# ST_LINK_V3E.net
KiCad netlist of a schematic drawn in Altium Designer
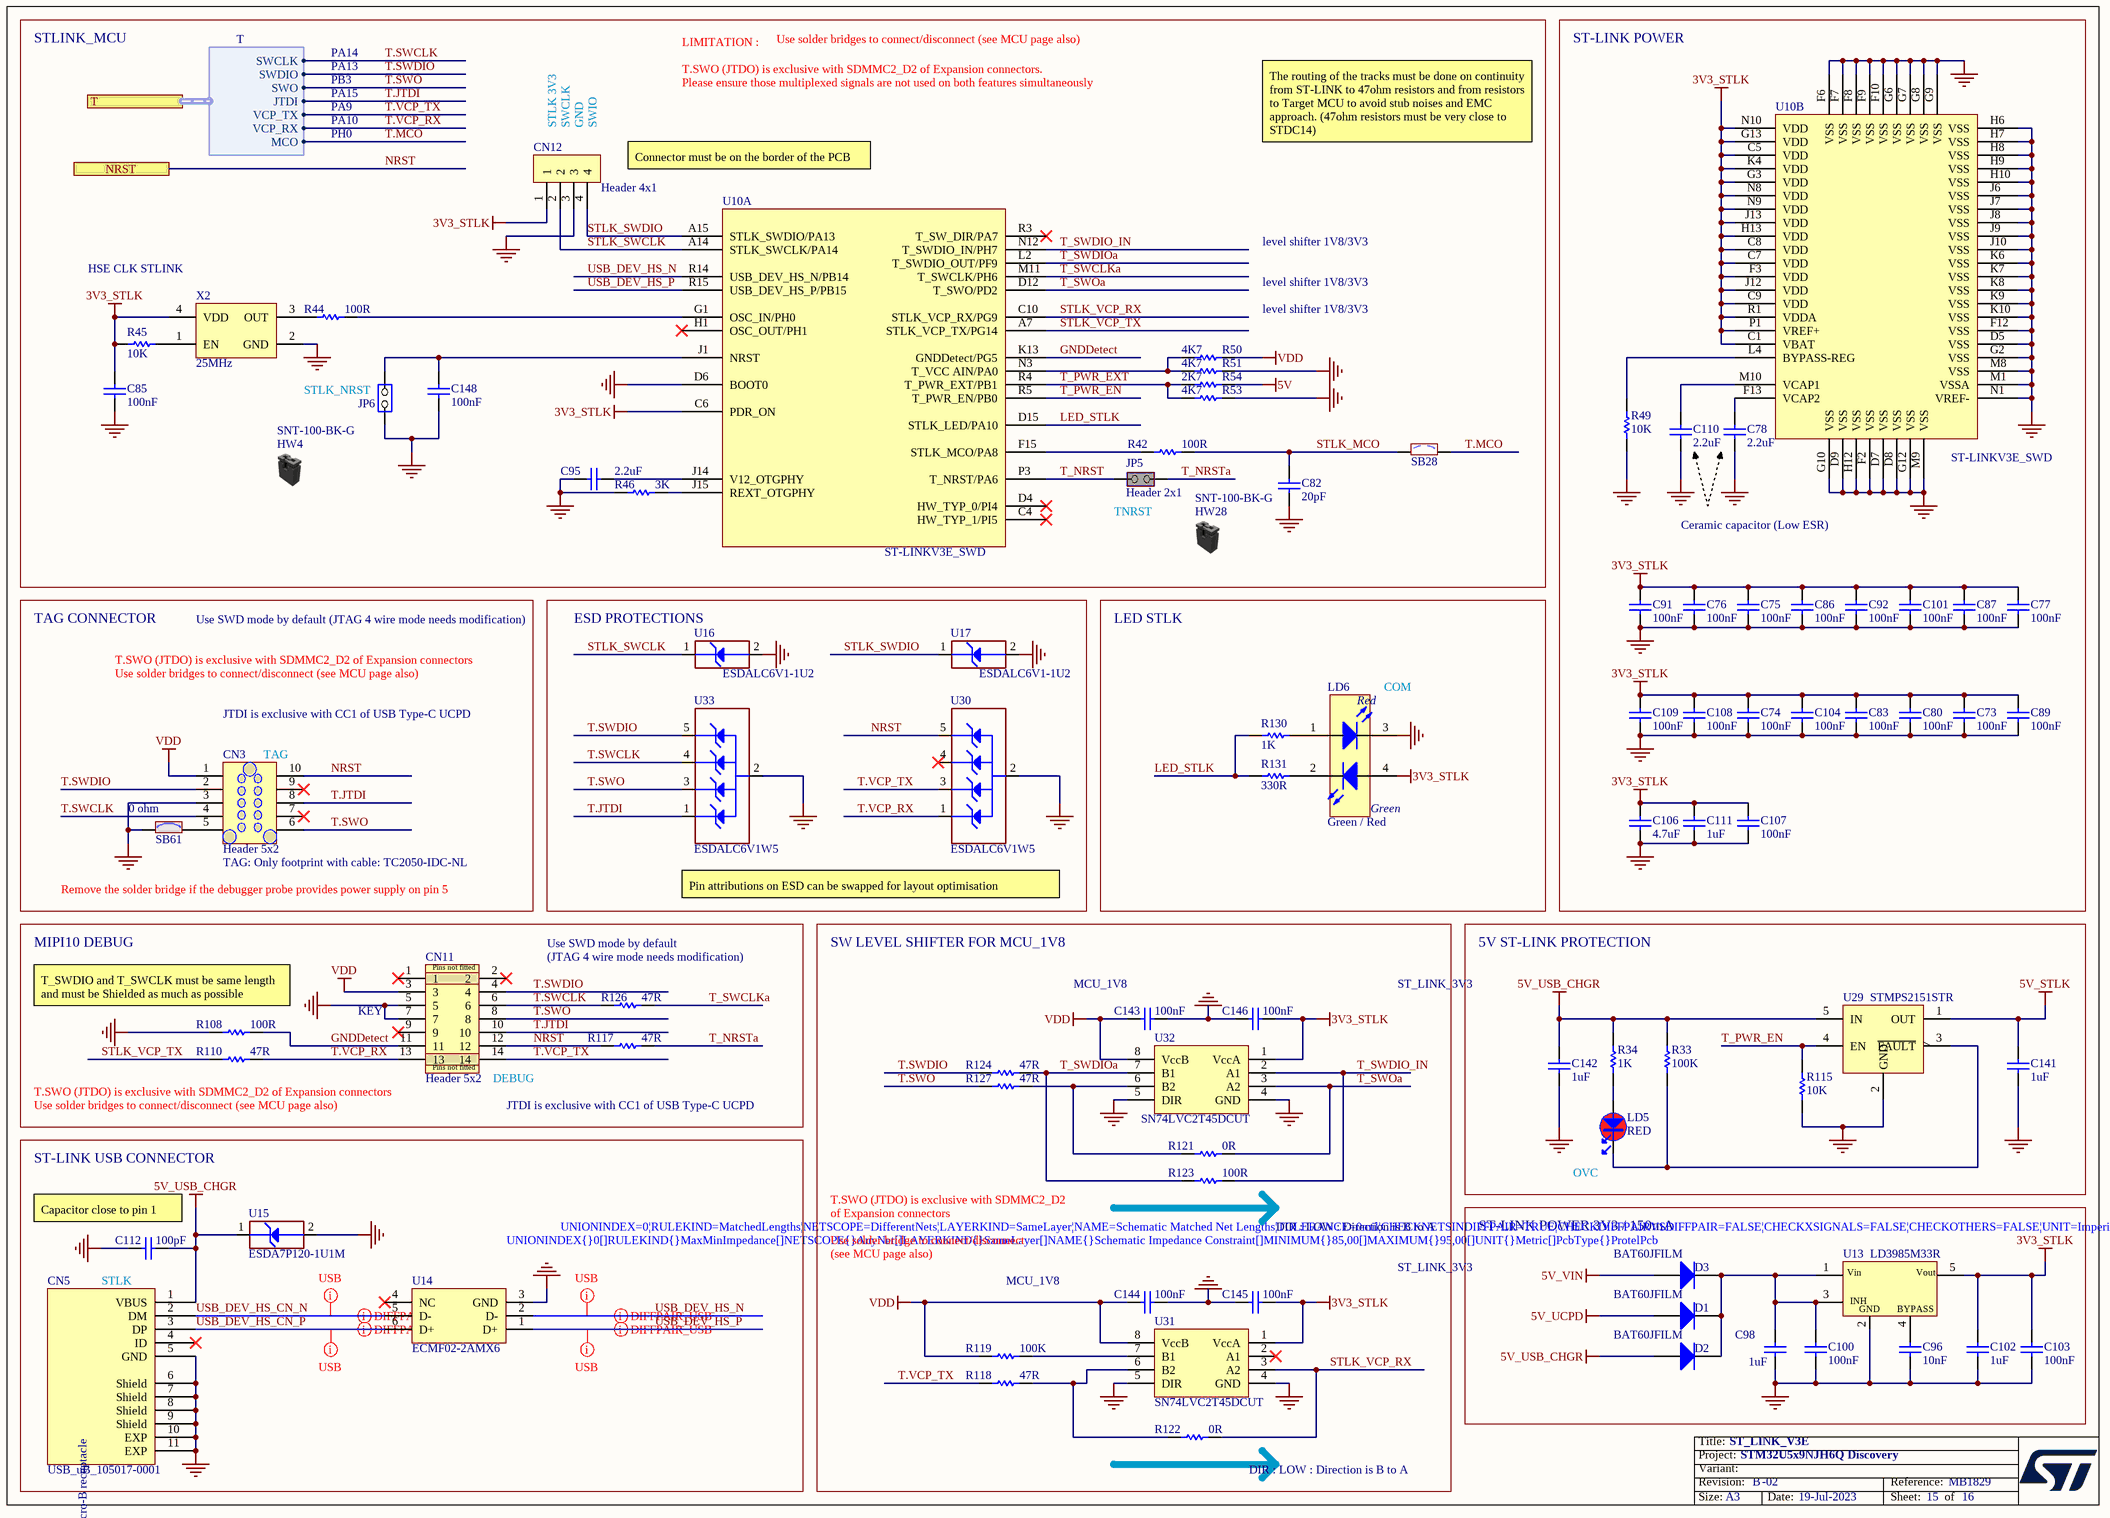
[diagram p0: ST_LINK_V3E.SchDoc]

(export (version "E")
  (design (tool "Eeschema 10.0.6"))
  (components
    (comp (ref "C73")
      (value "100nF")
      (footprint "MCD_PARTS:C0402")
      (description "Capacitor, MLCC, 100nF, 16V, X7R, +/-10%, 0402, T=0.5mm")
      (fields
        (field (name "INTERNAL_PART_NUMBER") "MCD-00006")
        (field (name "MANUFACTURER_PART_NUMBER") "CC0402KRX7R7BB104")
      )
      (libsource (lib "MCD_PARTS_database") (part "Capacitor"))
    )
    (comp (ref "C74")
      (value "100nF")
      (footprint "MCD_PARTS:C0402")
      (description "Capacitor, MLCC, 100nF, 16V, X7R, +/-10%, 0402, T=0.5mm")
      (fields
        (field (name "INTERNAL_PART_NUMBER") "MCD-00006")
        (field (name "MANUFACTURER_PART_NUMBER") "CC0402KRX7R7BB104")
      )
      (libsource (lib "MCD_PARTS_database") (part "Capacitor"))
    )
    (comp (ref "C75")
      (value "100nF")
      (footprint "MCD_PARTS:C0402")
      (description "Capacitor, MLCC, 100nF, 16V, X7R, +/-10%, 0402, T=0.5mm")
      (fields
        (field (name "INTERNAL_PART_NUMBER") "MCD-00006")
        (field (name "MANUFACTURER_PART_NUMBER") "CC0402KRX7R7BB104")
      )
      (libsource (lib "MCD_PARTS_database") (part "Capacitor"))
    )
    (comp (ref "C76")
      (value "100nF")
      (footprint "MCD_PARTS:C0402")
      (description "Capacitor, MLCC, 100nF, 16V, X7R, +/-10%, 0402, T=0.5mm")
      (fields
        (field (name "INTERNAL_PART_NUMBER") "MCD-00006")
        (field (name "MANUFACTURER_PART_NUMBER") "CC0402KRX7R7BB104")
      )
      (libsource (lib "MCD_PARTS_database") (part "Capacitor"))
    )
    (comp (ref "C77")
      (value "100nF")
      (footprint "MCD_PARTS:C0402")
      (description "Capacitor, MLCC, 100nF, 16V, X7R, +/-10%, 0402, T=0.5mm")
      (fields
        (field (name "INTERNAL_PART_NUMBER") "MCD-00006")
        (field (name "MANUFACTURER_PART_NUMBER") "CC0402KRX7R7BB104")
      )
      (libsource (lib "MCD_PARTS_database") (part "Capacitor"))
    )
    (comp (ref "C78")
      (value "2.2uF")
      (footprint "MCD_PARTS:C0603")
      (description "Capacitor, MLCC, 2.2uF, 10V, X5R, +/- 10%, 0603, T=0.8mm")
      (fields
        (field (name "INTERNAL_PART_NUMBER") "MCD-00012")
        (field (name "MANUFACTURER_PART_NUMBER") "CC0603KRX5R6BB225")
      )
      (libsource (lib "MCD_PARTS_database") (part "Capacitor"))
    )
    (comp (ref "C80")
      (value "100nF")
      (footprint "MCD_PARTS:C0402")
      (description "Capacitor, MLCC, 100nF, 16V, X7R, +/-10%, 0402, T=0.5mm")
      (fields
        (field (name "INTERNAL_PART_NUMBER") "MCD-00006")
        (field (name "MANUFACTURER_PART_NUMBER") "CC0402KRX7R7BB104")
      )
      (libsource (lib "MCD_PARTS_database") (part "Capacitor"))
    )
    (comp (ref "C82")
      (value "20pF")
      (footprint "MCD_PARTS:C0402")
      (description "Capacitor, MLCC, 20pF, 50V, NPO, +/- 5%, 0402, T=0.5mm")
      (fields
        (field (name "INTERNAL_PART_NUMBER") "MCD-00016")
        (field (name "MANUFACTURER_PART_NUMBER") "CC0402JRNPO9BN200")
      )
      (libsource (lib "MCD_PARTS_database") (part "Capacitor"))
    )
    (comp (ref "C83")
      (value "100nF")
      (footprint "MCD_PARTS:C0402")
      (description "Capacitor, MLCC, 100nF, 16V, X7R, +/-10%, 0402, T=0.5mm")
      (fields
        (field (name "INTERNAL_PART_NUMBER") "MCD-00006")
        (field (name "MANUFACTURER_PART_NUMBER") "CC0402KRX7R7BB104")
      )
      (libsource (lib "MCD_PARTS_database") (part "Capacitor"))
    )
    (comp (ref "C85")
      (value "100nF")
      (footprint "MCD_PARTS:C0402")
      (description "Capacitor, MLCC, 100nF, 16V, X7R, +/-10%, 0402, T=0.5mm")
      (fields
        (field (name "INTERNAL_PART_NUMBER") "MCD-00006")
        (field (name "MANUFACTURER_PART_NUMBER") "CC0402KRX7R7BB104")
      )
      (libsource (lib "MCD_PARTS_database") (part "Capacitor"))
    )
    (comp (ref "C86")
      (value "100nF")
      (footprint "MCD_PARTS:C0402")
      (description "Capacitor, MLCC, 100nF, 16V, X7R, +/-10%, 0402, T=0.5mm")
      (fields
        (field (name "INTERNAL_PART_NUMBER") "MCD-00006")
        (field (name "MANUFACTURER_PART_NUMBER") "CC0402KRX7R7BB104")
      )
      (libsource (lib "MCD_PARTS_database") (part "Capacitor"))
    )
    (comp (ref "C87")
      (value "100nF")
      (footprint "MCD_PARTS:C0402")
      (description "Capacitor, MLCC, 100nF, 16V, X7R, +/-10%, 0402, T=0.5mm")
      (fields
        (field (name "INTERNAL_PART_NUMBER") "MCD-00006")
        (field (name "MANUFACTURER_PART_NUMBER") "CC0402KRX7R7BB104")
      )
      (libsource (lib "MCD_PARTS_database") (part "Capacitor"))
    )
    (comp (ref "C89")
      (value "100nF")
      (footprint "MCD_PARTS:C0402")
      (description "Capacitor, MLCC, 100nF, 16V, X7R, +/-10%, 0402, T=0.5mm")
      (fields
        (field (name "INTERNAL_PART_NUMBER") "MCD-00006")
        (field (name "MANUFACTURER_PART_NUMBER") "CC0402KRX7R7BB104")
      )
      (libsource (lib "MCD_PARTS_database") (part "Capacitor"))
    )
    (comp (ref "C91")
      (value "100nF")
      (footprint "MCD_PARTS:C0402")
      (description "Capacitor, MLCC, 100nF, 16V, X7R, +/-10%, 0402, T=0.5mm")
      (fields
        (field (name "INTERNAL_PART_NUMBER") "MCD-00006")
        (field (name "MANUFACTURER_PART_NUMBER") "CC0402KRX7R7BB104")
      )
      (libsource (lib "MCD_PARTS_database") (part "Capacitor"))
    )
    (comp (ref "C92")
      (value "100nF")
      (footprint "MCD_PARTS:C0402")
      (description "Capacitor, MLCC, 100nF, 16V, X7R, +/-10%, 0402, T=0.5mm")
      (fields
        (field (name "INTERNAL_PART_NUMBER") "MCD-00006")
        (field (name "MANUFACTURER_PART_NUMBER") "CC0402KRX7R7BB104")
      )
      (libsource (lib "MCD_PARTS_database") (part "Capacitor"))
    )
    (comp (ref "C95")
      (value "2.2uF")
      (footprint "MCD_PARTS:C0603")
      (description "Capacitor, MLCC, 2.2uF, 10V, X5R, +/- 10%, 0603, T=0.8mm")
      (fields
        (field (name "INTERNAL_PART_NUMBER") "MCD-00012")
        (field (name "MANUFACTURER_PART_NUMBER") "CC0603KRX5R6BB225")
      )
      (libsource (lib "MCD_PARTS_database") (part "Capacitor"))
    )
    (comp (ref "C96")
      (value "10nF")
      (footprint "MCD_PARTS:C0402")
      (description "Capacitor, MLCC, 10nF, 16V, X7R, +/-10%, 0402, T=0.5mm")
      (fields
        (field (name "INTERNAL_PART_NUMBER") "MCD-00011")
        (field (name "MANUFACTURER_PART_NUMBER") "CC0402KRX7R7BB103")
      )
      (libsource (lib "MCD_PARTS_database") (part "Capacitor"))
    )
    (comp (ref "C98")
      (value "1uF")
      (footprint "MCD_PARTS:C0402")
      (description "Capacitor, MLCC, 1uF, 25V, X5R, +/-10%, 0402, T=0.5mm")
      (fields (field (name "INTERNAL_PART_NUMBER") "MCD-02609") (field (name "MANUFACTURER") "YAGEO"))
      (libsource (lib "MCD_PARTS_database") (part "Capacitor"))
    )
    (comp (ref "C100")
      (value "100nF")
      (footprint "MCD_PARTS:C0402")
      (description "Capacitor, MLCC, 100nF, 16V, X7R, +/-10%, 0402, T=0.5mm")
      (fields
        (field (name "INTERNAL_PART_NUMBER") "MCD-00006")
        (field (name "MANUFACTURER_PART_NUMBER") "CC0402KRX7R7BB104")
      )
      (libsource (lib "MCD_PARTS_database") (part "Capacitor"))
    )
    (comp (ref "C101")
      (value "100nF")
      (footprint "MCD_PARTS:C0402")
      (description "Capacitor, MLCC, 100nF, 16V, X7R, +/-10%, 0402, T=0.5mm")
      (fields
        (field (name "INTERNAL_PART_NUMBER") "MCD-00006")
        (field (name "MANUFACTURER_PART_NUMBER") "CC0402KRX7R7BB104")
      )
      (libsource (lib "MCD_PARTS_database") (part "Capacitor"))
    )
    (comp (ref "C102")
      (value "1uF")
      (footprint "MCD_PARTS:C0402")
      (description "Capacitor, MLCC, 1uF, 25V, X5R, +/-10%, 0402, T=0.5mm")
      (fields (field (name "INTERNAL_PART_NUMBER") "MCD-02609") (field (name "MANUFACTURER") "YAGEO"))
      (libsource (lib "MCD_PARTS_database") (part "Capacitor"))
    )
    (comp (ref "C103")
      (value "100nF")
      (footprint "MCD_PARTS:C0402")
      (description "Capacitor, MLCC, 100nF, 16V, X7R, +/-10%, 0402, T=0.5mm")
      (fields
        (field (name "INTERNAL_PART_NUMBER") "MCD-00006")
        (field (name "MANUFACTURER_PART_NUMBER") "CC0402KRX7R7BB104")
      )
      (libsource (lib "MCD_PARTS_database") (part "Capacitor"))
    )
    (comp (ref "C104")
      (value "100nF")
      (footprint "MCD_PARTS:C0402")
      (description "Capacitor, MLCC, 100nF, 16V, X7R, +/-10%, 0402, T=0.5mm")
      (fields
        (field (name "INTERNAL_PART_NUMBER") "MCD-00006")
        (field (name "MANUFACTURER_PART_NUMBER") "CC0402KRX7R7BB104")
      )
      (libsource (lib "MCD_PARTS_database") (part "Capacitor"))
    )
    (comp (ref "C106")
      (value "4.7uF")
      (footprint "MCD_PARTS:C0603")
      (description "Capacitor, MLCC, 4.7uF, 16V, X5R, +/-10%, 0603, T=0.8mm")
      (fields
        (field (name "INTERNAL_PART_NUMBER") "MCD-00009")
        (field (name "MANUFACTURER_PART_NUMBER") "CC0603KRX5R7BB475")
      )
      (libsource (lib "MCD_PARTS_database") (part "Capacitor"))
    )
    (comp (ref "C107")
      (value "100nF")
      (footprint "MCD_PARTS:C0402")
      (description "Capacitor, MLCC, 100nF, 16V, X7R, +/-10%, 0402, T=0.5mm")
      (fields
        (field (name "INTERNAL_PART_NUMBER") "MCD-00006")
        (field (name "MANUFACTURER_PART_NUMBER") "CC0402KRX7R7BB104")
      )
      (libsource (lib "MCD_PARTS_database") (part "Capacitor"))
    )
    (comp (ref "C108")
      (value "100nF")
      (footprint "MCD_PARTS:C0402")
      (description "Capacitor, MLCC, 100nF, 16V, X7R, +/-10%, 0402, T=0.5mm")
      (fields
        (field (name "INTERNAL_PART_NUMBER") "MCD-00006")
        (field (name "MANUFACTURER_PART_NUMBER") "CC0402KRX7R7BB104")
      )
      (libsource (lib "MCD_PARTS_database") (part "Capacitor"))
    )
    (comp (ref "C109")
      (value "100nF")
      (footprint "MCD_PARTS:C0402")
      (description "Capacitor, MLCC, 100nF, 16V, X7R, +/-10%, 0402, T=0.5mm")
      (fields
        (field (name "INTERNAL_PART_NUMBER") "MCD-00006")
        (field (name "MANUFACTURER_PART_NUMBER") "CC0402KRX7R7BB104")
      )
      (libsource (lib "MCD_PARTS_database") (part "Capacitor"))
    )
    (comp (ref "C110")
      (value "2.2uF")
      (footprint "MCD_PARTS:C0603")
      (description "Capacitor, MLCC, 2.2uF, 10V, X5R, +/- 10%, 0603, T=0.8mm")
      (fields
        (field (name "INTERNAL_PART_NUMBER") "MCD-00012")
        (field (name "MANUFACTURER_PART_NUMBER") "CC0603KRX5R6BB225")
      )
      (libsource (lib "MCD_PARTS_database") (part "Capacitor"))
    )
    (comp (ref "C111")
      (value "1uF")
      (footprint "MCD_PARTS:C0402")
      (description "Capacitor, MLCC, 1uF, 25V, X5R, +/-10%, 0402, T=0.5mm")
      (fields (field (name "INTERNAL_PART_NUMBER") "MCD-02609") (field (name "MANUFACTURER") "YAGEO"))
      (libsource (lib "MCD_PARTS_database") (part "Capacitor"))
    )
    (comp (ref "C112")
      (value "100pF")
      (footprint "MCD_PARTS:C0402")
      (description "Capacitor, MLCC, 100pF, 50V, NPO, +/-5%, 0402, T=0.5mm")
      (fields
        (field (name "INTERNAL_PART_NUMBER") "MCD-00205")
        (field (name "MANUFACTURER_PART_NUMBER") "CC0402JRNPO9BN101")
      )
      (libsource (lib "MCD_PARTS_database") (part "Capacitor"))
    )
    (comp (ref "C141")
      (value "1uF")
      (footprint "MCD_PARTS:C0402")
      (description "Capacitor, MLCC, 1uF, 25V, X5R, +/-10%, 0402, T=0.5mm")
      (fields (field (name "INTERNAL_PART_NUMBER") "MCD-02609") (field (name "MANUFACTURER") "YAGEO"))
      (libsource (lib "MCD_PARTS_database") (part "Capacitor"))
    )
    (comp (ref "C142")
      (value "1uF")
      (footprint "MCD_PARTS:C0402")
      (description "Capacitor, MLCC, 1uF, 25V, X5R, +/-10%, 0402, T=0.5mm")
      (fields (field (name "INTERNAL_PART_NUMBER") "MCD-02609") (field (name "MANUFACTURER") "YAGEO"))
      (libsource (lib "MCD_PARTS_database") (part "Capacitor"))
    )
    (comp (ref "C143")
      (value "100nF")
      (footprint "MCD_PARTS:C0402")
      (description "Capacitor, MLCC, 100nF, 16V, X7R, +/-10%, 0402, T=0.5mm")
      (fields
        (field (name "INTERNAL_PART_NUMBER") "MCD-00006")
        (field (name "MANUFACTURER_PART_NUMBER") "CC0402KRX7R7BB104")
      )
      (libsource (lib "MCD_PARTS_database") (part "Capacitor"))
    )
    (comp (ref "C144")
      (value "100nF")
      (footprint "MCD_PARTS:C0402")
      (description "Capacitor, MLCC, 100nF, 16V, X7R, +/-10%, 0402, T=0.5mm")
      (fields
        (field (name "INTERNAL_PART_NUMBER") "MCD-00006")
        (field (name "MANUFACTURER_PART_NUMBER") "CC0402KRX7R7BB104")
      )
      (libsource (lib "MCD_PARTS_database") (part "Capacitor"))
    )
    (comp (ref "C145")
      (value "100nF")
      (footprint "MCD_PARTS:C0402")
      (description "Capacitor, MLCC, 100nF, 16V, X7R, +/-10%, 0402, T=0.5mm")
      (fields
        (field (name "INTERNAL_PART_NUMBER") "MCD-00006")
        (field (name "MANUFACTURER_PART_NUMBER") "CC0402KRX7R7BB104")
      )
      (libsource (lib "MCD_PARTS_database") (part "Capacitor"))
    )
    (comp (ref "C146")
      (value "100nF")
      (footprint "MCD_PARTS:C0402")
      (description "Capacitor, MLCC, 100nF, 16V, X7R, +/-10%, 0402, T=0.5mm")
      (fields
        (field (name "INTERNAL_PART_NUMBER") "MCD-00006")
        (field (name "MANUFACTURER_PART_NUMBER") "CC0402KRX7R7BB104")
      )
      (libsource (lib "MCD_PARTS_database") (part "Capacitor"))
    )
    (comp (ref "C148")
      (value "100nF")
      (footprint "MCD_PARTS:C0402")
      (description "Capacitor, MLCC, 100nF, 16V, X7R, +/-10%, 0402, T=0.5mm")
      (fields
        (field (name "INTERNAL_PART_NUMBER") "MCD-00006")
        (field (name "MANUFACTURER_PART_NUMBER") "CC0402KRX7R7BB104")
      )
      (libsource (lib "MCD_PARTS_database") (part "Capacitor"))
    )
    (comp (ref "CN3")
      (value "Header 5x2")
      (footprint "MCD_PARTS:CON_TAG-C_TC2050-IDC-NL")
      (description "Header_Plug-of-nails, 5x2, 1.27mm, No legs")
      (fields
        (field (name "INTERNAL_PART_NUMBER") "MCD-00031")
        (field (name "MANUFACTURER_PART_NUMBER") "TC2050-IDC-NL-FP")
      )
      (libsource (lib "MCD_PARTS_database") (part "Tag-10-C"))
    )
    (comp (ref "CN5")
      (value "USB_uB_105017-0001")
      (footprint "MCD_PARTS:CON_USBMICROB_MOLEX_105017-0001_H2P90")
      (description "MicroUSB_TypeB, 5pins, 0.65mm, RA, SMD, T=2.9mm")
      (fields
        (field (name "INTERNAL_PART_NUMBER") "MCD-00028")
        (field (name "MANUFACTURER_PART_NUMBER") "1050170001")
      )
      (libsource (lib "MCD_PARTS_database") (part "USB_uB_105017.0001"))
    )
    (comp (ref "CN11")
      (value "Header 5x2")
      (footprint "MCD_PARTS:CON_STDC14_Receiver_MEDIUM__3D_FTSH-105-01-L-DV-K")
      (description "Header_MIPI10, 5x2, 1.27mm, VR, SMD, T=6.1mm")
      (fields (field (name "INTERNAL_PART_NUMBER") "MCD-02021") (field (name "MANUFACTURER") "SAMTEC"))
      (libsource (lib "MCD_PARTS_database") (part "Header 7x2_MIPI10_on_STDC14"))
    )
    (comp (ref "CN12")
      (value "Header 4x1")
      (footprint "MCD_PARTS:CON_SAMTEC_TSW-104-07-G-S")
      (description "Header, 4x1, 2.54mm, VR, TH, T=5.84mm/2.54mm")
      (fields
        (field (name "INTERNAL_PART_NUMBER") "MCD-00029")
        (field (name "MANUFACTURER_PART_NUMBER") "TSW-104-07-G-S")
      )
      (libsource (lib "MCD_PARTS_database") (part "Header 4x1"))
    )
    (comp (ref "D1")
      (value "BAT60JFILM")
      (footprint "MCD_PARTS:DIO_SOD323")
      (fields
        (field (name "INTERNAL_PART_NUMBER") "MCD-00034")
        (field (name "MANUFACTURER") "STMICROELECTRONICS")
        (field (name "BMS_PART_NUMBER") "9151097")
      )
      (libsource (lib "MCD_PARTS_database") (part "BAT60JFILM"))
    )
    (comp (ref "D2")
      (value "BAT60JFILM")
      (footprint "MCD_PARTS:DIO_SOD323")
      (fields
        (field (name "INTERNAL_PART_NUMBER") "MCD-00034")
        (field (name "MANUFACTURER") "STMICROELECTRONICS")
        (field (name "BMS_PART_NUMBER") "9151097")
      )
      (libsource (lib "MCD_PARTS_database") (part "BAT60JFILM"))
    )
    (comp (ref "D3")
      (value "BAT60JFILM")
      (footprint "MCD_PARTS:DIO_SOD323")
      (fields
        (field (name "INTERNAL_PART_NUMBER") "MCD-00034")
        (field (name "MANUFACTURER") "STMICROELECTRONICS")
        (field (name "BMS_PART_NUMBER") "9151097")
      )
      (libsource (lib "MCD_PARTS_database") (part "BAT60JFILM"))
    )
    (comp (ref "HW4")
      (value "SNT-100-BK-G")
      (description "SHUNT 2.54mm BLACK")
      (fields (field (name "INTERNAL_PART_NUMBER") "MCD-00043") (field (name "MANUFACTURER") "SAMTEC"))
      (libsource (lib "MCD_PARTS_database") (part "Shunt Black 2.54mm"))
    )
    (comp (ref "HW28")
      (value "SNT-100-BK-G")
      (description "SHUNT 2.54mm BLACK")
      (fields (field (name "INTERNAL_PART_NUMBER") "MCD-00043") (field (name "MANUFACTURER") "SAMTEC"))
      (libsource (lib "MCD_PARTS_database") (part "Shunt Black 2.54mm"))
    )
    (comp (ref "JP5")
      (value "Header 2x1")
      (footprint "MCD_PARTS:CON_SAMTEC_TSW-102-07-G-S")
      (description "Header, 2x1, 2.54mm, VR, TH, T=5.84mm/2.54mm")
      (fields (field (name "INTERNAL_PART_NUMBER") "MCD-01904") (field (name "MANUFACTURER") "SAMTEC"))
      (libsource (lib "MCD_PARTS_database") (part "Jumper_Header 2x1 Fitted"))
    )
    (comp (ref "JP6")
      (value "Jumper_Header 2x1")
      (footprint "MCD_PARTS:CON_SAMTEC_TSW-102-07-G-S")
      (description "Header, 2x1, 2.54mm, VR, TH, T=5.84mm/2.54mm")
      (fields
        (field (name "INTERNAL_PART_NUMBER") "MCD-00045")
        (field (name "MANUFACTURER_PART_NUMBER") "TSW-102-07-G-S")
      )
      (libsource (lib "MCD_PARTS_database") (part "Jumper_Header 2x1"))
    )
    (comp (ref "LD5")
      (value "RED")
      (footprint "MCD_PARTS:LED_0603_OSRAM_LS-Q976-NR-1_RED_1A2K_H0P8")
      (description "LED Red, 0603 SMD, Forward Voltage Typ=2V, Max=2.5V")
      (fields
        (field (name "INTERNAL_PART_NUMBER") "MCD-00586")
        (field (name "MANUFACTURER_PART_NUMBER") "LS Q976-NR-1")
      )
      (libsource (lib "MCD_PARTS_database") (part "LED_red"))
    )
    (comp (ref "LD6")
      (value "Green / Red")
      (footprint "LED_BI-GR_WE-150141SV73110")
      (description "LED Bicolor, Green/Red, 2V, 20mA,  4-PLCC")
      (fields
        (field (name "INTERNAL_PART_NUMBER") "MCD-02631")
        (field (name "MANUFACTURER") "WURTH ELEKTRONIK")
      )
      (libsource (lib "MCD_PARTS_database") (part "LED_BICOLOR"))
    )
    (comp (ref "R33")
      (value "100K")
      (footprint "MCD_PARTS:R0402")
      (description "Resistor, 100K, 0402, +/-1%, 1/16W")
      (fields
        (field (name "INTERNAL_PART_NUMBER") "MCD-00059")
        (field (name "MANUFACTURER_PART_NUMBER") "RC0402FR-07100KL")
      )
      (libsource (lib "MCD_PARTS_database") (part "Resistor"))
    )
    (comp (ref "R34")
      (value "1K")
      (footprint "MCD_PARTS:R0402")
      (description "Resistor, 1K, 0402, +/-1%,1/16W")
      (fields
        (field (name "INTERNAL_PART_NUMBER") "MCD-00061")
        (field (name "MANUFACTURER_PART_NUMBER") "RC0402FR-071KL")
      )
      (libsource (lib "MCD_PARTS_database") (part "Resistor"))
    )
    (comp (ref "R42")
      (value "100R")
      (footprint "MCD_PARTS:R0402")
      (description "Resistor, 100R, 0402, +/- 1%, 1/16W")
      (fields
        (field (name "INTERNAL_PART_NUMBER") "MCD-00067")
        (field (name "MANUFACTURER_PART_NUMBER") "RC0402FR-07100RL")
      )
      (libsource (lib "MCD_PARTS_database") (part "Resistor"))
    )
    (comp (ref "R44")
      (value "100R")
      (footprint "MCD_PARTS:R0402")
      (description "Resistor, 100R, 0402, +/- 1%, 1/16W")
      (fields
        (field (name "INTERNAL_PART_NUMBER") "MCD-00067")
        (field (name "MANUFACTURER_PART_NUMBER") "RC0402FR-07100RL")
      )
      (libsource (lib "MCD_PARTS_database") (part "Resistor"))
    )
    (comp (ref "R45")
      (value "10K")
      (footprint "MCD_PARTS:R0402")
      (description "Resistor, 10K, 0402, +/-1%, 1/16W")
      (fields
        (field (name "INTERNAL_PART_NUMBER") "MCD-00053")
        (field (name "MANUFACTURER_PART_NUMBER") "RC0402FR-0710KL")
      )
      (libsource (lib "MCD_PARTS_database") (part "Resistor"))
    )
    (comp (ref "R46")
      (value "3K")
      (footprint "MCD_PARTS:R0402")
      (description "Resistor, 3K, 0402, +/-1%, 1/16W")
      (fields
        (field (name "INTERNAL_PART_NUMBER") "MCD-00185")
        (field (name "MANUFACTURER_PART_NUMBER") "RC0402FR-073KL")
      )
      (libsource (lib "MCD_PARTS_database") (part "Resistor"))
    )
    (comp (ref "R49")
      (value "10K")
      (footprint "MCD_PARTS:R0402")
      (description "Resistor, 10K, 0402, +/-1%, 1/16W")
      (fields
        (field (name "INTERNAL_PART_NUMBER") "MCD-00053")
        (field (name "MANUFACTURER_PART_NUMBER") "RC0402FR-0710KL")
      )
      (libsource (lib "MCD_PARTS_database") (part "Resistor"))
    )
    (comp (ref "R50")
      (value "4K7")
      (footprint "MCD_PARTS:R0402")
      (description "Resistor, 4K7, 0402, +/-1%, 1/16W")
      (fields
        (field (name "INTERNAL_PART_NUMBER") "MCD-00065")
        (field (name "MANUFACTURER_PART_NUMBER") "RC0402FR-074K7L")
      )
      (libsource (lib "MCD_PARTS_database") (part "Resistor"))
    )
    (comp (ref "R51")
      (value "4K7")
      (footprint "MCD_PARTS:R0402")
      (description "Resistor, 4K7, 0402, +/-1%, 1/16W")
      (fields
        (field (name "INTERNAL_PART_NUMBER") "MCD-00065")
        (field (name "MANUFACTURER_PART_NUMBER") "RC0402FR-074K7L")
      )
      (libsource (lib "MCD_PARTS_database") (part "Resistor"))
    )
    (comp (ref "R53")
      (value "4K7")
      (footprint "MCD_PARTS:R0402")
      (description "Resistor, 4K7, 0402, +/-1%, 1/16W")
      (fields
        (field (name "INTERNAL_PART_NUMBER") "MCD-00065")
        (field (name "MANUFACTURER_PART_NUMBER") "RC0402FR-074K7L")
      )
      (libsource (lib "MCD_PARTS_database") (part "Resistor"))
    )
    (comp (ref "R54")
      (value "2K7")
      (footprint "MCD_PARTS:R0402")
      (description "Resistor, 2K7, 0402, +/-1%, 1/16W")
      (fields
        (field (name "INTERNAL_PART_NUMBER") "MCD-00055")
        (field (name "MANUFACTURER_PART_NUMBER") "RC0402FR-072K7L")
      )
      (libsource (lib "MCD_PARTS_database") (part "Resistor"))
    )
    (comp (ref "R108")
      (value "100R")
      (footprint "MCD_PARTS:R0402")
      (description "Resistor, 100R, 0402, +/- 1%, 1/16W")
      (fields
        (field (name "INTERNAL_PART_NUMBER") "MCD-00067")
        (field (name "MANUFACTURER_PART_NUMBER") "RC0402FR-07100RL")
      )
      (libsource (lib "MCD_PARTS_database") (part "Resistor"))
    )
    (comp (ref "R110")
      (value "47R")
      (footprint "MCD_PARTS:R0402")
      (description "Resistor, 47R, 0402, +/-1%, 1/16W")
      (fields
        (field (name "INTERNAL_PART_NUMBER") "MCD-00481")
        (field (name "MANUFACTURER_PART_NUMBER") "RC0402FR-0747RL")
      )
      (libsource (lib "MCD_PARTS_database") (part "Resistor"))
    )
    (comp (ref "R115")
      (value "10K")
      (footprint "MCD_PARTS:R0402")
      (description "Resistor, 10K, 0402, +/-1%, 1/16W")
      (fields
        (field (name "INTERNAL_PART_NUMBER") "MCD-00053")
        (field (name "MANUFACTURER_PART_NUMBER") "RC0402FR-0710KL")
      )
      (libsource (lib "MCD_PARTS_database") (part "Resistor"))
    )
    (comp (ref "R117")
      (value "47R")
      (footprint "MCD_PARTS:R0402")
      (description "Resistor, 47R, 0402, +/-1%, 1/16W")
      (fields
        (field (name "INTERNAL_PART_NUMBER") "MCD-00481")
        (field (name "MANUFACTURER_PART_NUMBER") "RC0402FR-0747RL")
      )
      (libsource (lib "MCD_PARTS_database") (part "Resistor"))
    )
    (comp (ref "R118")
      (value "47R")
      (footprint "MCD_PARTS:R0402")
      (description "Resistor, 47R, 0402, +/-1%, 1/16W")
      (fields
        (field (name "INTERNAL_PART_NUMBER") "MCD-00481")
        (field (name "MANUFACTURER_PART_NUMBER") "RC0402FR-0747RL")
      )
      (libsource (lib "MCD_PARTS_database") (part "Resistor"))
    )
    (comp (ref "R119")
      (value "100K")
      (footprint "MCD_PARTS:R0402")
      (description "Resistor, 100K, 0402, +/-1%, 1/16W")
      (fields
        (field (name "INTERNAL_PART_NUMBER") "MCD-00059")
        (field (name "MANUFACTURER_PART_NUMBER") "RC0402FR-07100KL")
      )
      (libsource (lib "MCD_PARTS_database") (part "Resistor"))
    )
    (comp (ref "R121")
      (value "0R")
      (footprint "MCD_PARTS:R0402")
      (description "Resistor, 0R, 0402, +/-5%, 1/16W")
      (fields
        (field (name "INTERNAL_PART_NUMBER") "MCD-00052")
        (field (name "MANUFACTURER_PART_NUMBER") "RC0402JR-070RL")
      )
      (libsource (lib "MCD_PARTS_database") (part "Resistor"))
    )
    (comp (ref "R122")
      (value "0R")
      (footprint "MCD_PARTS:R0402")
      (description "Resistor, 0R, 0402, +/-5%, 1/16W")
      (fields
        (field (name "INTERNAL_PART_NUMBER") "MCD-00052")
        (field (name "MANUFACTURER_PART_NUMBER") "RC0402JR-070RL")
      )
      (libsource (lib "MCD_PARTS_database") (part "Resistor"))
    )
    (comp (ref "R123")
      (value "100R")
      (footprint "MCD_PARTS:R0402")
      (description "Resistor, 100R, 0402, +/- 1%, 1/16W")
      (fields
        (field (name "INTERNAL_PART_NUMBER") "MCD-00067")
        (field (name "MANUFACTURER_PART_NUMBER") "RC0402FR-07100RL")
      )
      (libsource (lib "MCD_PARTS_database") (part "Resistor"))
    )
    (comp (ref "R124")
      (value "47R")
      (footprint "MCD_PARTS:R0402")
      (description "Resistor, 47R, 0402, +/-1%, 1/16W")
      (fields
        (field (name "INTERNAL_PART_NUMBER") "MCD-00481")
        (field (name "MANUFACTURER_PART_NUMBER") "RC0402FR-0747RL")
      )
      (libsource (lib "MCD_PARTS_database") (part "Resistor"))
    )
    (comp (ref "R126")
      (value "47R")
      (footprint "MCD_PARTS:R0402")
      (description "Resistor, 47R, 0402, +/-1%, 1/16W")
      (fields
        (field (name "INTERNAL_PART_NUMBER") "MCD-00481")
        (field (name "MANUFACTURER_PART_NUMBER") "RC0402FR-0747RL")
      )
      (libsource (lib "MCD_PARTS_database") (part "Resistor"))
    )
    (comp (ref "R127")
      (value "47R")
      (footprint "MCD_PARTS:R0402")
      (description "Resistor, 47R, 0402, +/-1%, 1/16W")
      (fields
        (field (name "INTERNAL_PART_NUMBER") "MCD-00481")
        (field (name "MANUFACTURER_PART_NUMBER") "RC0402FR-0747RL")
      )
      (libsource (lib "MCD_PARTS_database") (part "Resistor"))
    )
    (comp (ref "R130")
      (value "1K")
      (footprint "MCD_PARTS:R0402")
      (description "Resistor, 1K, 0402, +/-1%,1/16W")
      (fields
        (field (name "INTERNAL_PART_NUMBER") "MCD-00061")
        (field (name "MANUFACTURER_PART_NUMBER") "RC0402FR-071KL")
      )
      (libsource (lib "MCD_PARTS_database") (part "Resistor"))
    )
    (comp (ref "R131")
      (value "330R")
      (footprint "MCD_PARTS:R0402")
      (description "Resistor, 330R, 0402, +/-1%, 1/16W")
      (fields
        (field (name "INTERNAL_PART_NUMBER") "MCD-00062")
        (field (name "MANUFACTURER_PART_NUMBER") "RC0402FR-07330RL")
      )
      (libsource (lib "MCD_PARTS_database") (part "Resistor"))
    )
    (comp (ref "SB28")
      (value "SB_OFF")
      (footprint "MCD_PARTS:SOLDER-BRIDGE_R0402-0R")
      (description "Solder Bridge 0402 OFF")
      (fields
        (field (name "INTERNAL_PART_NUMBER") "MCD-02162")
        (field (name "MANUFACTURER_PART_NUMBER") "RC0402JR-070RL")
      )
      (libsource (lib "MCD_PARTS_database") (part "SB_OFF"))
    )
    (comp (ref "SB61")
      (value "0 ohm")
      (footprint "SOLDER-BRIDGE_R0402-0R")
      (description "Solder Bridge 0402 ON")
      (fields (field (name "INTERNAL_PART_NUMBER") "MCD-01618") (field (name "MANUFACTURER") "YAGEO"))
      (libsource (lib "MCD_PARTS_database") (part "SB_ON"))
    )
    (comp (ref "U10")
      (value "ST-LINKV3E_SWD")
      (footprint "MCD_PARTS:ICC_UFBGA201_176+25_10X10_P065")
      (description "STM32F723IEK  (STM32F7) BGA176")
      (fields
        (field (name "INTERNAL_PART_NUMBER") "MCD-00596")
        (field (name "MANUFACTURER_PART_NUMBER") "STM32F723IEK6")
      )
      (libsource (lib "MCD_PARTS_database") (part "ST-LINKV3E_SWD"))
    )
    (comp (ref "U13")
      (value "LD3985M33R")
      (footprint "MCD_PARTS:REG_SOT23-5L")
      (description "Ultra low drop-low noise BiCMOS voltage, regulators low ESR capacitors compatible")
      (fields
        (field (name "INTERNAL_PART_NUMBER") "MCD-00086")
        (field (name "MANUFACTURER") "STMICROELECTRONICS")
      )
      (libsource (lib "MCD_PARTS_database") (part "LD3985M33R"))
    )
    (comp (ref "U14")
      (value "ECMF02-2AMX6")
      (footprint "MCD_PARTS:ESD_QFN-6L_1P7X1P5_P050")
      (description "Common mode filter with ESD protection for USB 2.0 interface")
      (fields
        (field (name "INTERNAL_PART_NUMBER") "MCD-00649")
        (field (name "MANUFACTURER") "STMICROELECTRONICS")
      )
      (libsource (lib "MCD_PARTS_database") (part "ECMF02-2AMX6"))
    )
    (comp (ref "U15")
      (value "ESDA7P120-1U1M")
      (footprint "MCD_PARTS:ESD_QFN1610_2N_1K_2A")
      (description "High power transient voltage suppressor")
      (fields
        (field (name "INTERNAL_PART_NUMBER") "MCD-01026")
        (field (name "MANUFACTURER") "STMICROELECTRONICS")
      )
      (libsource (lib "MCD_PARTS_database") (part "ESD-TRANSIL"))
    )
    (comp (ref "U16")
      (value "ESDALC6V1-1U2")
      (footprint "MCD_PARTS:ESD_ST0201")
      (description "ESD protection 6V1")
      (fields
        (field (name "INTERNAL_PART_NUMBER") "MCD-00170")
        (field (name "MANUFACTURER") "STMICROELECTRONICS")
      )
      (libsource (lib "MCD_PARTS_database") (part "ESD-TRANSIL"))
    )
    (comp (ref "U17")
      (value "ESDALC6V1-1U2")
      (footprint "MCD_PARTS:ESD_ST0201")
      (description "ESD protection 6V1")
      (fields
        (field (name "INTERNAL_PART_NUMBER") "MCD-00170")
        (field (name "MANUFACTURER") "STMICROELECTRONICS")
      )
      (libsource (lib "MCD_PARTS_database") (part "ESD-TRANSIL"))
    )
    (comp (ref "U29")
      (value "STMPS2151STR")
      (footprint "MCD_PARTS:MOS_SOT23-5L")
      (description "500mA, Enhanced single channel power switches with active high enable pin")
      (fields
        (field (name "INTERNAL_PART_NUMBER") "MCD-00159")
        (field (name "MANUFACTURER") "STMICROELECTRONICS")
      )
      (libsource (lib "MCD_PARTS_database") (part "STMPS2151STR"))
    )
    (comp (ref "U30")
      (value "ESDALC6V1W5")
      (footprint "MCD_PARTS:ESD_SOT323-5L")
      (description "Dual Transil array for ESD protection")
      (fields
        (field (name "INTERNAL_PART_NUMBER") "MCD-00136")
        (field (name "MANUFACTURER") "STMICROELECTRONICS")
      )
      (libsource (lib "MCD_PARTS_database") (part "ESDALC6V1W5"))
    )
    (comp (ref "U31")
      (value "SN74LVC2T45DCUT")
      (footprint "MCD_PARTS:ICC_VSSOP8_DCU_R-PDSO-G8_2X2P30_P050")
      (description "Dual bit dual supply bus transceiver")
      (fields
        (field (name "INTERNAL_PART_NUMBER") "MCD-00264")
        (field (name "MANUFACTURER") "TEXAS INSTRUMENTS")
      )
      (libsource (lib "MCD_PARTS_database") (part "SN74LVC2T45DCUT"))
    )
    (comp (ref "U32")
      (value "SN74LVC2T45DCUT")
      (footprint "MCD_PARTS:ICC_VSSOP8_DCU_R-PDSO-G8_2X2P30_P050")
      (description "Dual bit dual supply bus transceiver")
      (fields
        (field (name "INTERNAL_PART_NUMBER") "MCD-00264")
        (field (name "MANUFACTURER") "TEXAS INSTRUMENTS")
      )
      (libsource (lib "MCD_PARTS_database") (part "SN74LVC2T45DCUT"))
    )
    (comp (ref "U33")
      (value "ESDALC6V1W5")
      (footprint "MCD_PARTS:ESD_SOT323-5L")
      (description "Dual Transil array for ESD protection")
      (fields
        (field (name "INTERNAL_PART_NUMBER") "MCD-00136")
        (field (name "MANUFACTURER") "STMICROELECTRONICS")
      )
      (libsource (lib "MCD_PARTS_database") (part "ESDALC6V1W5"))
    )
    (comp (ref "X2")
      (value "25MHz")
      (footprint "MCD_PARTS:OSC_NDK_NZ2520SB_4P")
      (description "Oscillator, SPXO, 25Mhz, +/-50ppm, 3V3, square wave, 2.5x2mm")
      (fields
        (field (name "INTERNAL_PART_NUMBER") "MCD-00597")
        (field (name "MANUFACTURER_PART_NUMBER") "NZ2520SH-25MHZ-END4869C")
      )
      (libsource (lib "MCD_PARTS_database") (part "OSCILLATOR_4_PINS"))
    )
  )
  (nets
    (net (code "2") (name "/GNDDetect") (class "Default")
      (node (ref "CN11") (pin "11") (pinfunction "11_11") (pintype "passive"))
      (node (ref "R108") (pin "2") (pinfunction "2_2") (pintype "passive"))
      (node (ref "U10") (pin "K13") (pinfunction "GNDDetect/PG5_K13") (pintype "passive"))
    )
    (net (code "3") (name "/LED_STLK") (class "Default")
      (node (ref "R130") (pin "2") (pinfunction "2_2") (pintype "passive"))
      (node (ref "R131") (pin "2") (pinfunction "2_2") (pintype "passive"))
      (node (ref "U10") (pin "D15") (pinfunction "STLK_LED/PA10_D15") (pintype "passive"))
    )
    (net (code "4") (name "/NRST") (class "Default")
      (node (ref "CN11") (pin "12") (pinfunction "12_12") (pintype "passive"))
      (node (ref "CN3") (pin "10") (pinfunction "10_10") (pintype "passive"))
      (node (ref "R117") (pin "1") (pinfunction "1_1") (pintype "passive"))
      (node (ref "U30") (pin "5") (pinfunction "IO4_5") (pintype "passive"))
    )
    (net (code "5") (name "/STLK_MCO") (class "Default")
      (node (ref "C82") (pin "2") (pinfunction "2_2") (pintype "passive"))
      (node (ref "R42") (pin "2") (pinfunction "2_2") (pintype "passive"))
      (node (ref "SB28") (pin "1") (pinfunction "1_1") (pintype "passive"))
    )
    (net (code "6") (name "/STLK_SWCLK") (class "Default")
      (node (ref "CN12") (pin "2") (pinfunction "2_2") (pintype "passive"))
      (node (ref "U10") (pin "A14") (pinfunction "STLK_SWCLK/PA14_A14") (pintype "passive"))
      (node (ref "U16") (pin "1") (pinfunction "IO1_1") (pintype "passive"))
    )
    (net (code "7") (name "/STLK_SWDIO") (class "Default")
      (node (ref "CN12") (pin "4") (pinfunction "4_4") (pintype "passive"))
      (node (ref "U10") (pin "A15") (pinfunction "STLK_SWDIO/PA13_A15") (pintype "passive"))
      (node (ref "U17") (pin "1") (pinfunction "IO1_1") (pintype "passive"))
    )
    (net (code "8") (name "/STLK_VCP_RX") (class "Default")
      (node (ref "R122") (pin "2") (pinfunction "2_2") (pintype "passive"))
      (node (ref "U10") (pin "C10") (pinfunction "STLK_VCP_RX/PG9_C10") (pintype "passive"))
      (node (ref "U31") (pin "3") (pinfunction "A2_3") (pintype "passive"))
    )
    (net (code "9") (name "/STLK_VCP_TX") (class "Default")
      (node (ref "R110") (pin "1") (pinfunction "1_1") (pintype "passive"))
      (node (ref "U10") (pin "A7") (pinfunction "STLK_VCP_TX/PG14_A7") (pintype "passive"))
    )
    (net (code "10") (name "/T.JTDI") (class "Default")
      (node (ref "CN11") (pin "10") (pinfunction "10_10") (pintype "passive"))
      (node (ref "CN3") (pin "8") (pinfunction "8_8") (pintype "passive"))
      (node (ref "U33") (pin "1") (pinfunction "IO1_1") (pintype "passive"))
    )
    (net (code "11") (name "/T.MCO") (class "Default")
      (node (ref "SB28") (pin "2") (pinfunction "2_2") (pintype "passive"))
    )
    (net (code "12") (name "/T.SWCLK") (class "Default")
      (node (ref "CN11") (pin "6") (pinfunction "6_6") (pintype "passive"))
      (node (ref "CN3") (pin "4") (pinfunction "4_4") (pintype "passive"))
      (node (ref "R126") (pin "1") (pinfunction "1_1") (pintype "passive"))
      (node (ref "U33") (pin "4") (pinfunction "IO3_4") (pintype "passive"))
    )
    (net (code "13") (name "/T.SWDIO") (class "Default")
      (node (ref "CN11") (pin "4") (pinfunction "4_4") (pintype "passive"))
      (node (ref "CN3") (pin "2") (pinfunction "2_2") (pintype "passive"))
      (node (ref "R124") (pin "1") (pinfunction "1_1") (pintype "passive"))
      (node (ref "U33") (pin "5") (pinfunction "IO4_5") (pintype "passive"))
    )
    (net (code "14") (name "/T.SWO") (class "Default")
      (node (ref "CN11") (pin "8") (pinfunction "8_8") (pintype "passive"))
      (node (ref "CN3") (pin "6") (pinfunction "6_6") (pintype "passive"))
      (node (ref "R127") (pin "1") (pinfunction "1_1") (pintype "passive"))
      (node (ref "U33") (pin "3") (pinfunction "IO2_3") (pintype "passive"))
    )
    (net (code "15") (name "/T.VCP_RX") (class "Default")
      (node (ref "CN11") (pin "13") (pinfunction "13_13") (pintype "passive"))
      (node (ref "R110") (pin "2") (pinfunction "2_2") (pintype "passive"))
      (node (ref "U30") (pin "1") (pinfunction "IO1_1") (pintype "passive"))
    )
    (net (code "16") (name "/T.VCP_TX") (class "Default")
      (node (ref "CN11") (pin "14") (pinfunction "14_14") (pintype "passive"))
      (node (ref "R118") (pin "1") (pinfunction "1_1") (pintype "passive"))
      (node (ref "U30") (pin "3") (pinfunction "IO2_3") (pintype "passive"))
    )
    (net (code "17") (name "/T_NRST") (class "Default")
      (node (ref "JP5") (pin "1") (pinfunction "COMMON_1") (pintype "passive"))
      (node (ref "U10") (pin "P3") (pinfunction "T_NRST/PA6_P3") (pintype "passive"))
    )
    (net (code "18") (name "/T_NRSTa") (class "Default")
      (node (ref "JP5") (pin "2") (pinfunction "NO_2") (pintype "passive"))
      (node (ref "R117") (pin "2") (pinfunction "2_2") (pintype "passive"))
    )
    (net (code "19") (name "/T_PWR_EN") (class "Default")
      (node (ref "R115") (pin "2") (pinfunction "2_2") (pintype "passive"))
      (node (ref "U10") (pin "R5") (pinfunction "T_PWR_EN/PB0_R5") (pintype "passive"))
      (node (ref "U29") (pin "4") (pinfunction "EN_4") (pintype "passive"))
    )
    (net (code "20") (name "/T_PWR_EXT") (class "Default")
      (node (ref "R53") (pin "2") (pinfunction "2_2") (pintype "passive"))
      (node (ref "R54") (pin "2") (pinfunction "2_2") (pintype "passive"))
      (node (ref "U10") (pin "R4") (pinfunction "T_PWR_EXT/PB1_R4") (pintype "passive"))
    )
    (net (code "21") (name "/T_SWCLKa") (class "Default")
      (node (ref "R126") (pin "2") (pinfunction "2_2") (pintype "passive"))
      (node (ref "U10") (pin "M11") (pinfunction "T_SWCLK/PH6_M11") (pintype "passive"))
    )
    (net (code "22") (name "/T_SWDIO_IN") (class "Default")
      (node (ref "R123") (pin "2") (pinfunction "2_2") (pintype "passive"))
      (node (ref "U10") (pin "N12") (pinfunction "T_SWDIO_IN/PH7_N12") (pintype "passive"))
      (node (ref "U32") (pin "2") (pinfunction "A1_2") (pintype "passive"))
    )
    (net (code "23") (name "/T_SWDIOa") (class "Default")
      (node (ref "R123") (pin "1") (pinfunction "1_1") (pintype "passive"))
      (node (ref "R124") (pin "2") (pinfunction "2_2") (pintype "passive"))
      (node (ref "U10") (pin "L2") (pinfunction "T_SWDIO_OUT/PF9_L2") (pintype "passive"))
      (node (ref "U32") (pin "7") (pinfunction "B1_7") (pintype "passive"))
    )
    (net (code "24") (name "/T_SWOa") (class "Default")
      (node (ref "R121") (pin "2") (pinfunction "2_2") (pintype "passive"))
      (node (ref "U10") (pin "D12") (pinfunction "T_SWO/PD2_D12") (pintype "passive"))
      (node (ref "U32") (pin "3") (pinfunction "A2_3") (pintype "passive"))
    )
    (net (code "25") (name "/USB_DEV_HS_CN_N") (class "Default")
      (node (ref "CN5") (pin "2") (pinfunction "DM_2") (pintype "passive"))
      (node (ref "U14") (pin "5") (pinfunction "D-_5") (pintype "passive"))
    )
    (net (code "26") (name "/USB_DEV_HS_CN_P") (class "Default")
      (node (ref "CN5") (pin "3") (pinfunction "DP_3") (pintype "passive"))
      (node (ref "U14") (pin "6") (pinfunction "D+_6") (pintype "passive"))
    )
    (net (code "27") (name "/USB_DEV_HS_N") (class "Default")
      (node (ref "U10") (pin "R14") (pinfunction "USB_DEV_HS_N/PB14_R14") (pintype "passive"))
      (node (ref "U14") (pin "2") (pinfunction "D-_2") (pintype "passive"))
    )
    (net (code "28") (name "/USB_DEV_HS_P") (class "Default")
      (node (ref "U10") (pin "R15") (pinfunction "USB_DEV_HS_P/PB15_R15") (pintype "passive"))
      (node (ref "U14") (pin "1") (pinfunction "D+_1") (pintype "passive"))
    )
    (net (code "30") (name "3V3_STLK") (class "Default")
      (node (ref "C101") (pin "1") (pinfunction "1_1") (pintype "passive"))
      (node (ref "C102") (pin "2") (pinfunction "2_2") (pintype "passive"))
      (node (ref "C103") (pin "2") (pinfunction "2_2") (pintype "passive"))
      (node (ref "C104") (pin "1") (pinfunction "1_1") (pintype "passive"))
      (node (ref "C106") (pin "2") (pinfunction "2_2") (pintype "passive"))
      (node (ref "C107") (pin "1") (pinfunction "1_1") (pintype "passive"))
      (node (ref "C108") (pin "1") (pinfunction "1_1") (pintype "passive"))
      (node (ref "C109") (pin "1") (pinfunction "1_1") (pintype "passive"))
      (node (ref "C111") (pin "2") (pinfunction "2_2") (pintype "passive"))
      (node (ref "C145") (pin "2") (pinfunction "2_2") (pintype "passive"))
      (node (ref "C146") (pin "2") (pinfunction "2_2") (pintype "passive"))
      (node (ref "C73") (pin "1") (pinfunction "1_1") (pintype "passive"))
      (node (ref "C74") (pin "1") (pinfunction "1_1") (pintype "passive"))
      (node (ref "C75") (pin "1") (pinfunction "1_1") (pintype "passive"))
      (node (ref "C76") (pin "1") (pinfunction "1_1") (pintype "passive"))
      (node (ref "C77") (pin "1") (pinfunction "1_1") (pintype "passive"))
      (node (ref "C80") (pin "1") (pinfunction "1_1") (pintype "passive"))
      (node (ref "C83") (pin "1") (pinfunction "1_1") (pintype "passive"))
      (node (ref "C85") (pin "1") (pinfunction "1_1") (pintype "passive"))
      (node (ref "C86") (pin "1") (pinfunction "1_1") (pintype "passive"))
      (node (ref "C87") (pin "1") (pinfunction "1_1") (pintype "passive"))
      (node (ref "C89") (pin "1") (pinfunction "1_1") (pintype "passive"))
      (node (ref "C91") (pin "1") (pinfunction "1_1") (pintype "passive"))
      (node (ref "C92") (pin "1") (pinfunction "1_1") (pintype "passive"))
      (node (ref "CN12") (pin "1") (pinfunction "1_1") (pintype "passive"))
      (node (ref "LD6") (pin "4") (pinfunction "Green_anode_4") (pintype "passive"))
      (node (ref "R45") (pin "1") (pinfunction "1_1") (pintype "passive"))
      (node (ref "U10") (pin "C1") (pinfunction "VBAT_C1") (pintype "passive"))
      (node (ref "U10") (pin "C5") (pinfunction "VDD_C5") (pintype "passive"))
      (node (ref "U10") (pin "C6") (pinfunction "PDR_ON_C6") (pintype "passive"))
      (node (ref "U10") (pin "C7") (pinfunction "VDD_C7") (pintype "passive"))
      (node (ref "U10") (pin "C8") (pinfunction "VDD_C8") (pintype "passive"))
      (node (ref "U10") (pin "C9") (pinfunction "VDD_C9") (pintype "passive"))
      (node (ref "U10") (pin "F3") (pinfunction "VDD_F3") (pintype "passive"))
      (node (ref "U10") (pin "G13") (pinfunction "VDD_G13") (pintype "passive"))
      (node (ref "U10") (pin "G3") (pinfunction "VDD_G3") (pintype "passive"))
      (node (ref "U10") (pin "H13") (pinfunction "VDD_H13") (pintype "passive"))
      (node (ref "U10") (pin "J12") (pinfunction "VDD_J12") (pintype "passive"))
      (node (ref "U10") (pin "J13") (pinfunction "VDD_J13") (pintype "passive"))
      (node (ref "U10") (pin "K4") (pinfunction "VDD_K4") (pintype "passive"))
      (node (ref "U10") (pin "N10") (pinfunction "VDD_N10") (pintype "passive"))
      (node (ref "U10") (pin "N8") (pinfunction "VDD_N8") (pintype "passive"))
      (node (ref "U10") (pin "N9") (pinfunction "VDD_N9") (pintype "passive"))
      (node (ref "U10") (pin "P1") (pinfunction "VREF+_P1") (pintype "passive"))
      (node (ref "U10") (pin "R1") (pinfunction "VDDA_R1") (pintype "passive"))
      (node (ref "U13") (pin "5") (pinfunction "Vout_5") (pintype "passive"))
      (node (ref "U31") (pin "1") (pinfunction "VccA_1") (pintype "power_in"))
      (node (ref "U32") (pin "1") (pinfunction "VccA_1") (pintype "power_in"))
      (node (ref "X2") (pin "4") (pinfunction "VDD_4") (pintype "passive"))
    )
    (net (code "31") (name "5V") (class "Default")
      (node (ref "R54") (pin "1") (pinfunction "1_1") (pintype "passive"))
    )
    (net (code "32") (name "5V_STLK") (class "Default")
      (node (ref "C141") (pin "2") (pinfunction "2_2") (pintype "passive"))
      (node (ref "U29") (pin "1") (pinfunction "OUT_1") (pintype "passive"))
    )
    (net (code "33") (name "5V_UCPD") (class "Default")
      (node (ref "D1") (pin "1") (pinfunction "A_1") (pintype "passive"))
    )
    (net (code "34") (name "5V_USB_CHGR") (class "Default")
      (node (ref "C112") (pin "2") (pinfunction "2_2") (pintype "passive"))
      (node (ref "C142") (pin "2") (pinfunction "2_2") (pintype "passive"))
      (node (ref "CN5") (pin "1") (pinfunction "VBUS_1") (pintype "passive"))
      (node (ref "D2") (pin "1") (pinfunction "A_1") (pintype "passive"))
      (node (ref "R33") (pin "2") (pinfunction "2_2") (pintype "passive"))
      (node (ref "R34") (pin "2") (pinfunction "2_2") (pintype "passive"))
      (node (ref "U15") (pin "1") (pinfunction "IO1_1") (pintype "passive"))
      (node (ref "U29") (pin "5") (pinfunction "IN_5") (pintype "passive"))
    )
    (net (code "35") (name "5V_VIN") (class "Default")
      (node (ref "D3") (pin "1") (pinfunction "A_1") (pintype "passive"))
    )
    (net (code "36") (name "GND") (class "Default")
      (node (ref "C100") (pin "1") (pinfunction "1_1") (pintype "passive"))
      (node (ref "C101") (pin "2") (pinfunction "2_2") (pintype "passive"))
      (node (ref "C102") (pin "1") (pinfunction "1_1") (pintype "passive"))
      (node (ref "C103") (pin "1") (pinfunction "1_1") (pintype "passive"))
      (node (ref "C104") (pin "2") (pinfunction "2_2") (pintype "passive"))
      (node (ref "C106") (pin "1") (pinfunction "1_1") (pintype "passive"))
      (node (ref "C107") (pin "2") (pinfunction "2_2") (pintype "passive"))
      (node (ref "C108") (pin "2") (pinfunction "2_2") (pintype "passive"))
      (node (ref "C109") (pin "2") (pinfunction "2_2") (pintype "passive"))
      (node (ref "C110") (pin "1") (pinfunction "1_1") (pintype "passive"))
      (node (ref "C111") (pin "1") (pinfunction "1_1") (pintype "passive"))
      (node (ref "C112") (pin "1") (pinfunction "1_1") (pintype "passive"))
      (node (ref "C141") (pin "1") (pinfunction "1_1") (pintype "passive"))
      (node (ref "C142") (pin "1") (pinfunction "1_1") (pintype "passive"))
      (node (ref "C143") (pin "2") (pinfunction "2_2") (pintype "passive"))
      (node (ref "C144") (pin "2") (pinfunction "2_2") (pintype "passive"))
      (node (ref "C145") (pin "1") (pinfunction "1_1") (pintype "passive"))
      (node (ref "C146") (pin "1") (pinfunction "1_1") (pintype "passive"))
      (node (ref "C148") (pin "2") (pinfunction "2_2") (pintype "passive"))
      (node (ref "C73") (pin "2") (pinfunction "2_2") (pintype "passive"))
      (node (ref "C74") (pin "2") (pinfunction "2_2") (pintype "passive"))
      (node (ref "C75") (pin "2") (pinfunction "2_2") (pintype "passive"))
      (node (ref "C76") (pin "2") (pinfunction "2_2") (pintype "passive"))
      (node (ref "C77") (pin "2") (pinfunction "2_2") (pintype "passive"))
      (node (ref "C78") (pin "1") (pinfunction "1_1") (pintype "passive"))
      (node (ref "C80") (pin "2") (pinfunction "2_2") (pintype "passive"))
      (node (ref "C82") (pin "1") (pinfunction "1_1") (pintype "passive"))
      (node (ref "C83") (pin "2") (pinfunction "2_2") (pintype "passive"))
      (node (ref "C85") (pin "2") (pinfunction "2_2") (pintype "passive"))
      (node (ref "C86") (pin "2") (pinfunction "2_2") (pintype "passive"))
      (node (ref "C87") (pin "2") (pinfunction "2_2") (pintype "passive"))
      (node (ref "C89") (pin "2") (pinfunction "2_2") (pintype "passive"))
      (node (ref "C91") (pin "2") (pinfunction "2_2") (pintype "passive"))
      (node (ref "C92") (pin "2") (pinfunction "2_2") (pintype "passive"))
      (node (ref "C95") (pin "1") (pinfunction "1_1") (pintype "passive"))
      (node (ref "C96") (pin "1") (pinfunction "1_1") (pintype "passive"))
      (node (ref "C98") (pin "1") (pinfunction "1_1") (pintype "passive"))
      (node (ref "CN11") (pin "5") (pinfunction "5_5") (pintype "passive"))
      (node (ref "CN11") (pin "7") (pinfunction "7_7") (pintype "passive"))
      (node (ref "CN12") (pin "3") (pinfunction "3_3") (pintype "passive"))
      (node (ref "CN3") (pin "3") (pinfunction "3_3") (pintype "passive"))
      (node (ref "CN5") (pin "10") (pinfunction "EXP_10") (pintype "passive"))
      (node (ref "CN5") (pin "11") (pinfunction "EXP_11") (pintype "passive"))
      (node (ref "CN5") (pin "5") (pinfunction "GND_5") (pintype "passive"))
      (node (ref "CN5") (pin "6") (pinfunction "Shield_6") (pintype "passive"))
      (node (ref "CN5") (pin "7") (pinfunction "Shield_7") (pintype "passive"))
      (node (ref "CN5") (pin "8") (pinfunction "Shield_8") (pintype "passive"))
      (node (ref "CN5") (pin "9") (pinfunction "Shield_9") (pintype "passive"))
      (node (ref "JP6") (pin "1") (pinfunction "COMMON_1") (pintype "passive"))
      (node (ref "LD6") (pin "3") (pinfunction "RED_cathode_3") (pintype "passive"))
      (node (ref "R108") (pin "1") (pinfunction "1_1") (pintype "passive"))
      (node (ref "R115") (pin "1") (pinfunction "1_1") (pintype "passive"))
      (node (ref "R46") (pin "1") (pinfunction "1_1") (pintype "passive"))
      (node (ref "R49") (pin "1") (pinfunction "1_1") (pintype "passive"))
      (node (ref "R51") (pin "2") (pinfunction "2_2") (pintype "passive"))
      (node (ref "R53") (pin "1") (pinfunction "1_1") (pintype "passive"))
      (node (ref "SB61") (pin "1") (pinfunction "1_1") (pintype "passive"))
      (node (ref "U10") (pin "D5") (pinfunction "VSS_D5") (pintype "passive"))
      (node (ref "U10") (pin "D6") (pinfunction "BOOT0_D6") (pintype "passive"))
      (node (ref "U10") (pin "D7") (pinfunction "VSS_D7") (pintype "passive"))
      (node (ref "U10") (pin "D8") (pinfunction "VSS_D8") (pintype "passive"))
      (node (ref "U10") (pin "D9") (pinfunction "VSS_D9") (pintype "passive"))
      (node (ref "U10") (pin "F10") (pinfunction "VSS_F10") (pintype "passive"))
      (node (ref "U10") (pin "F12") (pinfunction "VSS_F12") (pintype "passive"))
      (node (ref "U10") (pin "F2") (pinfunction "VSS_F2") (pintype "passive"))
      (node (ref "U10") (pin "F6") (pinfunction "VSS_F6") (pintype "passive"))
      (node (ref "U10") (pin "F7") (pinfunction "VSS_F7") (pintype "passive"))
      (node (ref "U10") (pin "F8") (pinfunction "VSS_F8") (pintype "passive"))
      (node (ref "U10") (pin "F9") (pinfunction "VSS_F9") (pintype "passive"))
      (node (ref "U10") (pin "G10") (pinfunction "VSS_G10") (pintype "passive"))
      (node (ref "U10") (pin "G12") (pinfunction "VSS_G12") (pintype "passive"))
      (node (ref "U10") (pin "G2") (pinfunction "VSS_G2") (pintype "passive"))
      (node (ref "U10") (pin "G6") (pinfunction "VSS_G6") (pintype "passive"))
      (node (ref "U10") (pin "G7") (pinfunction "VSS_G7") (pintype "passive"))
      (node (ref "U10") (pin "G8") (pinfunction "VSS_G8") (pintype "passive"))
      (node (ref "U10") (pin "G9") (pinfunction "VSS_G9") (pintype "passive"))
      (node (ref "U10") (pin "H10") (pinfunction "VSS_H10") (pintype "passive"))
      (node (ref "U10") (pin "H12") (pinfunction "VSS_H12") (pintype "passive"))
      (node (ref "U10") (pin "H6") (pinfunction "VSS_H6") (pintype "passive"))
      (node (ref "U10") (pin "H7") (pinfunction "VSS_H7") (pintype "passive"))
      (node (ref "U10") (pin "H8") (pinfunction "VSS_H8") (pintype "passive"))
      (node (ref "U10") (pin "H9") (pinfunction "VSS_H9") (pintype "passive"))
      (node (ref "U10") (pin "J10") (pinfunction "VSS_J10") (pintype "passive"))
      (node (ref "U10") (pin "J6") (pinfunction "VSS_J6") (pintype "passive"))
      (node (ref "U10") (pin "J7") (pinfunction "VSS_J7") (pintype "passive"))
      (node (ref "U10") (pin "J8") (pinfunction "VSS_J8") (pintype "passive"))
      (node (ref "U10") (pin "J9") (pinfunction "VSS_J9") (pintype "passive"))
      (node (ref "U10") (pin "K10") (pinfunction "VSS_K10") (pintype "passive"))
      (node (ref "U10") (pin "K6") (pinfunction "VSS_K6") (pintype "passive"))
      (node (ref "U10") (pin "K7") (pinfunction "VSS_K7") (pintype "passive"))
      (node (ref "U10") (pin "K8") (pinfunction "VSS_K8") (pintype "passive"))
      (node (ref "U10") (pin "K9") (pinfunction "VSS_K9") (pintype "passive"))
      (node (ref "U10") (pin "M1") (pinfunction "VSSA_M1") (pintype "passive"))
      (node (ref "U10") (pin "M8") (pinfunction "VSS_M8") (pintype "passive"))
      (node (ref "U10") (pin "M9") (pinfunction "VSS_M9") (pintype "passive"))
      (node (ref "U10") (pin "N1") (pinfunction "VREF-_N1") (pintype "passive"))
      (node (ref "U13") (pin "2") (pinfunction "GND_2") (pintype "passive"))
      (node (ref "U14") (pin "3") (pinfunction "GND_3") (pintype "passive"))
      (node (ref "U15") (pin "2") (pinfunction "GND_2") (pintype "passive"))
      (node (ref "U16") (pin "2") (pinfunction "GND_2") (pintype "passive"))
      (node (ref "U17") (pin "2") (pinfunction "GND_2") (pintype "passive"))
      (node (ref "U29") (pin "2") (pinfunction "GND_2") (pintype "passive"))
      (node (ref "U30") (pin "2") (pinfunction "GND_2") (pintype "passive"))
      (node (ref "U31") (pin "4") (pinfunction "GND_4") (pintype "power_in"))
      (node (ref "U31") (pin "5") (pinfunction "DIR_5") (pintype "passive"))
      (node (ref "U32") (pin "4") (pinfunction "GND_4") (pintype "power_in"))
      (node (ref "U32") (pin "5") (pinfunction "DIR_5") (pintype "passive"))
      (node (ref "U33") (pin "2") (pinfunction "GND_2") (pintype "passive"))
      (node (ref "X2") (pin "2") (pinfunction "GND_2") (pintype "passive"))
    )
    (net (code "37") (name "Net-(CN3-Pad5)") (class "Default")
      (node (ref "CN3") (pin "5") (pinfunction "5_5") (pintype "passive"))
      (node (ref "SB61") (pin "2") (pinfunction "2_2") (pintype "passive"))
    )
    (net (code "38") (name "Net-(D1-K)") (class "Default")
      (node (ref "C100") (pin "2") (pinfunction "2_2") (pintype "passive"))
      (node (ref "C98") (pin "2") (pinfunction "2_2") (pintype "passive"))
      (node (ref "D1") (pin "2") (pinfunction "K_2") (pintype "passive"))
      (node (ref "D2") (pin "2") (pinfunction "K_2") (pintype "passive"))
      (node (ref "D3") (pin "2") (pinfunction "K_2") (pintype "passive"))
      (node (ref "U13") (pin "1") (pinfunction "Vin_1") (pintype "passive"))
      (node (ref "U13") (pin "3") (pinfunction "CE_3") (pintype "passive"))
    )
    (net (code "39") (name "Net-(JP6-NO)") (class "Default")
      (node (ref "C148") (pin "1") (pinfunction "1_1") (pintype "passive"))
      (node (ref "JP6") (pin "2") (pinfunction "NO_2") (pintype "passive"))
      (node (ref "U10") (pin "J1") (pinfunction "NRST_J1") (pintype "passive"))
    )
    (net (code "40") (name "Net-(LD5-Pad1)") (class "Default")
      (node (ref "LD5") (pin "1") (pintype "passive"))
      (node (ref "R34") (pin "1") (pinfunction "1_1") (pintype "passive"))
    )
    (net (code "41") (name "Net-(LD6-Green_cathode)") (class "Default")
      (node (ref "LD6") (pin "2") (pinfunction "Green_cathode_2") (pintype "passive"))
      (node (ref "R131") (pin "1") (pinfunction "1_1") (pintype "passive"))
    )
    (net (code "42") (name "Net-(LD6-Red_anode)") (class "Default")
      (node (ref "LD6") (pin "1") (pinfunction "Red_anode_1") (pintype "passive"))
      (node (ref "R130") (pin "1") (pinfunction "1_1") (pintype "passive"))
    )
    (net (code "43") (name "Net-(U10A-OSC_IN{slash}PH0)") (class "Default")
      (node (ref "R44") (pin "2") (pinfunction "2_2") (pintype "passive"))
      (node (ref "U10") (pin "G1") (pinfunction "OSC_IN/PH0_G1") (pintype "passive"))
    )
    (net (code "44") (name "Net-(U10A-REXT_OTGPHY)") (class "Default")
      (node (ref "R46") (pin "2") (pinfunction "2_2") (pintype "passive"))
      (node (ref "U10") (pin "J15") (pinfunction "REXT_OTGPHY_J15") (pintype "passive"))
    )
    (net (code "45") (name "Net-(U10A-STLK_MCO{slash}PA8)") (class "Default")
      (node (ref "R42") (pin "1") (pinfunction "1_1") (pintype "passive"))
      (node (ref "U10") (pin "F15") (pinfunction "STLK_MCO/PA8_F15") (pintype "passive"))
    )
    (net (code "46") (name "Net-(U10A-T_VCC_AIN{slash}PA0)") (class "Default")
      (node (ref "R50") (pin "1") (pinfunction "1_1") (pintype "passive"))
      (node (ref "R51") (pin "1") (pinfunction "1_1") (pintype "passive"))
      (node (ref "U10") (pin "N3") (pinfunction "T_VCC_AIN/PA0_N3") (pintype "passive"))
    )
    (net (code "47") (name "Net-(U10A-V12_OTGPHY)") (class "Default")
      (node (ref "C95") (pin "2") (pinfunction "2_2") (pintype "passive"))
      (node (ref "U10") (pin "J14") (pinfunction "V12_OTGPHY_J14") (pintype "passive"))
    )
    (net (code "48") (name "Net-(U10B-BYPASS-REG)") (class "Default")
      (node (ref "R49") (pin "2") (pinfunction "2_2") (pintype "passive"))
      (node (ref "U10") (pin "L4") (pinfunction "BYPASS-REG_L4") (pintype "passive"))
    )
    (net (code "49") (name "Net-(U10B-VCAP1)") (class "Default")
      (node (ref "C110") (pin "2") (pinfunction "2_2") (pintype "passive"))
      (node (ref "U10") (pin "M10") (pinfunction "VCAP1_M10") (pintype "passive"))
    )
    (net (code "50") (name "Net-(U10B-VCAP2)") (class "Default")
      (node (ref "C78") (pin "2") (pinfunction "2_2") (pintype "passive"))
      (node (ref "U10") (pin "F13") (pinfunction "VCAP2_F13") (pintype "passive"))
    )
    (net (code "51") (name "Net-(U13-BYPASS)") (class "Default")
      (node (ref "C96") (pin "2") (pinfunction "2_2") (pintype "passive"))
      (node (ref "U13") (pin "4") (pinfunction "BYPASS_4") (pintype "passive"))
    )
    (net (code "52") (name "Net-(U29-~{FAULT})") (class "Default")
      (node (ref "LD5") (pin "2") (pintype "passive"))
      (node (ref "R33") (pin "1") (pinfunction "1_1") (pintype "passive"))
      (node (ref "U29") (pin "3") (pinfunction "~{FAULT}_3") (pintype "passive"))
    )
    (net (code "53") (name "Net-(U31-B1)") (class "Default")
      (node (ref "R119") (pin "2") (pinfunction "2_2") (pintype "passive"))
      (node (ref "U31") (pin "7") (pinfunction "B1_7") (pintype "passive"))
    )
    (net (code "54") (name "Net-(U31-B2)") (class "Default")
      (node (ref "R118") (pin "2") (pinfunction "2_2") (pintype "passive"))
      (node (ref "R122") (pin "1") (pinfunction "1_1") (pintype "passive"))
      (node (ref "U31") (pin "6") (pinfunction "B2_6") (pintype "passive"))
    )
    (net (code "55") (name "Net-(U32-B2)") (class "Default")
      (node (ref "R121") (pin "1") (pinfunction "1_1") (pintype "passive"))
      (node (ref "R127") (pin "2") (pinfunction "2_2") (pintype "passive"))
      (node (ref "U32") (pin "6") (pinfunction "B2_6") (pintype "passive"))
    )
    (net (code "56") (name "Net-(X2-EN)") (class "Default")
      (node (ref "R45") (pin "2") (pinfunction "2_2") (pintype "passive"))
      (node (ref "X2") (pin "1") (pinfunction "EN_1") (pintype "passive"))
    )
    (net (code "57") (name "Net-(X2-OUT)") (class "Default")
      (node (ref "R44") (pin "1") (pinfunction "1_1") (pintype "passive"))
      (node (ref "X2") (pin "3") (pinfunction "OUT_3") (pintype "passive"))
    )
    (net (code "58") (name "VDD") (class "Default")
      (node (ref "C143") (pin "1") (pinfunction "1_1") (pintype "passive"))
      (node (ref "C144") (pin "1") (pinfunction "1_1") (pintype "passive"))
      (node (ref "CN11") (pin "3") (pinfunction "3_3") (pintype "passive"))
      (node (ref "CN3") (pin "1") (pinfunction "1_1") (pintype "passive"))
      (node (ref "R119") (pin "1") (pinfunction "1_1") (pintype "passive"))
      (node (ref "R50") (pin "2") (pinfunction "2_2") (pintype "passive"))
      (node (ref "U31") (pin "8") (pinfunction "VccB_8") (pintype "power_in"))
      (node (ref "U32") (pin "8") (pinfunction "VccB_8") (pintype "power_in"))
    )
    (net (code "59") (name "unconnected-(CN3-Pad7)") (class "Default")
      (node (ref "CN3") (pin "7") (pinfunction "7_7") (pintype "passive+no_connect"))
    )
    (net (code "60") (name "unconnected-(CN3-Pad9)") (class "Default")
      (node (ref "CN3") (pin "9") (pinfunction "9_9") (pintype "passive+no_connect"))
    )
    (net (code "61") (name "unconnected-(CN5-ID-Pad4)") (class "Default")
      (node (ref "CN5") (pin "4") (pinfunction "ID_4") (pintype "passive+no_connect"))
    )
    (net (code "62") (name "unconnected-(CN11-Pad1)") (class "Default")
      (node (ref "CN11") (pin "1") (pinfunction "1_1") (pintype "passive+no_connect"))
    )
    (net (code "63") (name "unconnected-(CN11-Pad2)") (class "Default")
      (node (ref "CN11") (pin "2") (pinfunction "2_2") (pintype "passive+no_connect"))
    )
    (net (code "64") (name "unconnected-(CN11-Pad9)") (class "Default")
      (node (ref "CN11") (pin "9") (pinfunction "9_9") (pintype "passive+no_connect"))
    )
    (net (code "65") (name "unconnected-(U10A-HW_TYP_0{slash}PI4-PadD4)") (class "Default")
      (node (ref "U10") (pin "D4") (pinfunction "HW_TYP_0/PI4_D4") (pintype "passive+no_connect"))
    )
    (net (code "66") (name "unconnected-(U10A-HW_TYP_1{slash}PI5-PadC4)") (class "Default")
      (node (ref "U10") (pin "C4") (pinfunction "HW_TYP_1/PI5_C4") (pintype "passive+no_connect"))
    )
    (net (code "67") (name "unconnected-(U10A-OSC_OUT{slash}PH1-PadH1)") (class "Default")
      (node (ref "U10") (pin "H1") (pinfunction "OSC_OUT/PH1_H1") (pintype "passive+no_connect"))
    )
    (net (code "68") (name "unconnected-(U10A-T_SW_DIR{slash}PA7-PadR3)") (class "Default")
      (node (ref "U10") (pin "R3") (pinfunction "T_SW_DIR/PA7_R3") (pintype "passive+no_connect"))
    )
    (net (code "69") (name "unconnected-(U14-NC-Pad4)") (class "Default")
      (node (ref "U14") (pin "4") (pinfunction "NC_4") (pintype "passive+no_connect"))
    )
    (net (code "70") (name "unconnected-(U30-IO3-Pad4)") (class "Default")
      (node (ref "U30") (pin "4") (pinfunction "IO3_4") (pintype "passive+no_connect"))
    )
    (net (code "71") (name "unconnected-(U31-A1-Pad2)") (class "Default")
      (node (ref "U31") (pin "2") (pinfunction "A1_2") (pintype "passive+no_connect"))
    )
  )
)
